# shield_SIM800L_2.net
KiCad netlist of a schematic drawn in EAGLE
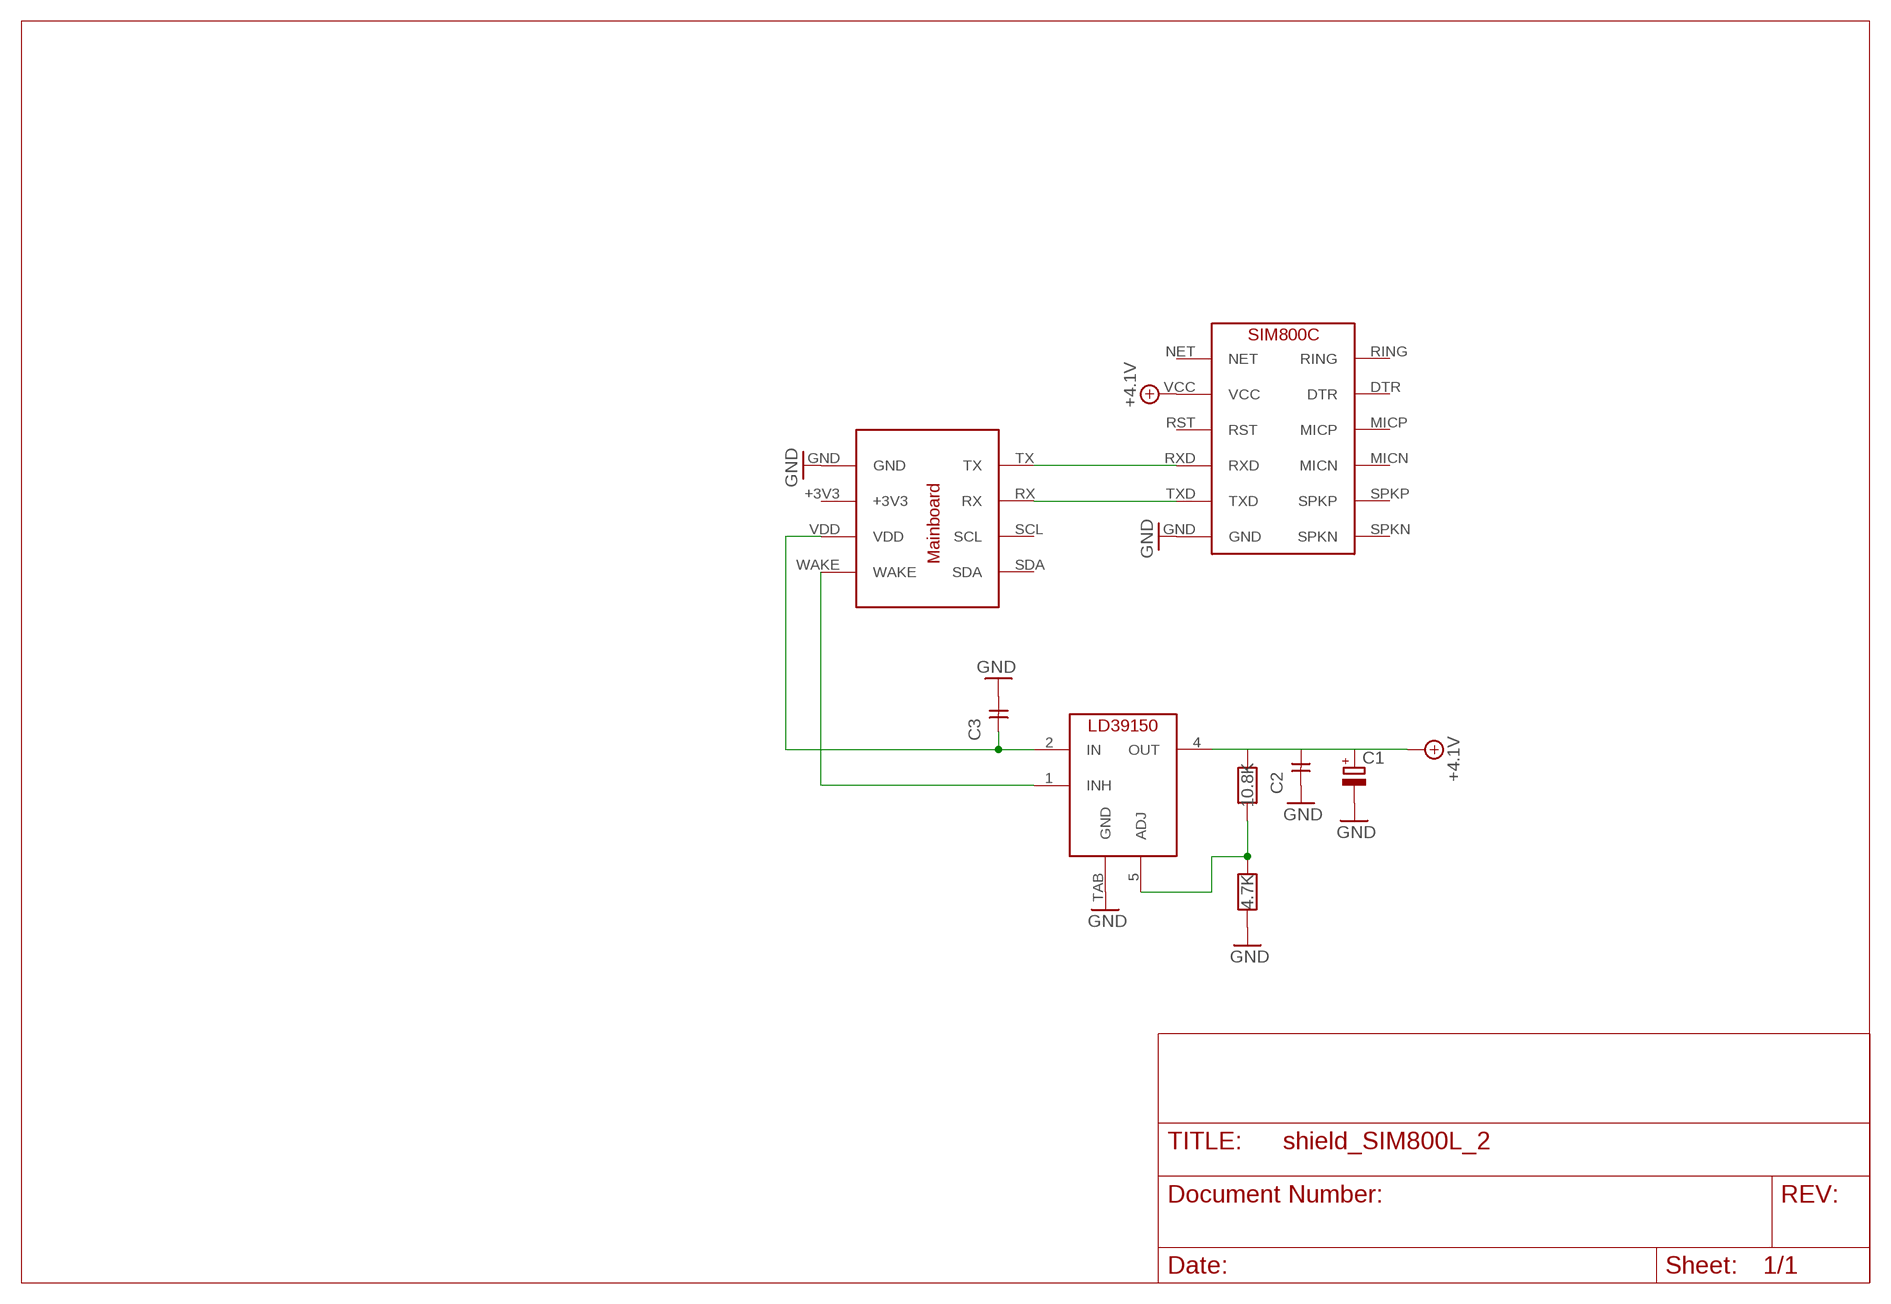
[diagram p0: schematic, sheet 1]

(export (version "E")
  (design (tool "Eeschema 10.0.6"))
  (components
    (comp (ref "C1")
      (value "CPOL-EUE5-13")
      (footprint "eagle-import:E5-13")
      (libsource (lib "eagle-import") (part "CPOL-EUE5-13"))
    )
    (comp (ref "C2")
      (value "CSMD_1206")
      (footprint "eagle-import:SMD_RC_1206")
      (libsource (lib "eagle-import") (part "CSMD_1206"))
    )
    (comp (ref "C3")
      (value "CSMD_1206")
      (footprint "eagle-import:SMD_RC_1206")
      (libsource (lib "eagle-import") (part "CSMD_1206"))
    )
    (comp (ref "R1")
      (value "10.8K")
      (footprint "eagle-import:SMD_RC_1206")
      (libsource (lib "eagle-import") (part "RSMD_1206"))
    )
    (comp (ref "R2")
      (value "4.7K")
      (footprint "eagle-import:SMD_RC_1206")
      (libsource (lib "eagle-import") (part "RSMD_1206"))
    )
    (comp (ref "U$1")
      (value "SHIELD")
      (footprint "eagle-import:SHIELD")
      (libsource (lib "eagle-import") (part "SHIELD"))
    )
    (comp (ref "U$2")
      (value "LD39150PT-R")
      (footprint "eagle-import:PPAK")
      (libsource (lib "eagle-import") (part "LD39150PT-R"))
    )
    (comp (ref "U$6")
      (value "SIM800L")
      (footprint "eagle-import:SIM800L")
      (libsource (lib "eagle-import") (part "SIM800L"))
    )
  )
  (nets
    (net (code "1") (name "+4.1V") (class "Default")
      (node (ref "C1") (pin "+") (pinfunction "+_+") (pintype "passive"))
      (node (ref "C2") (pin "P$2") (pinfunction "2_P$2") (pintype "passive"))
      (node (ref "R1") (pin "P$1") (pinfunction "P$1_P$1") (pintype "passive"))
      (node (ref "U$2") (pin "4") (pinfunction "OUT_4") (pintype "power_in"))
      (node (ref "U$6") (pin "VCC") (pinfunction "VCC_VCC") (pintype "bidirectional"))
    )
    (net (code "2") (name "/+3V3") (class "Default")
      (node (ref "U$1") (pin "+3V3") (pinfunction "+3V3_+3V3") (pintype "power_in"))
    )
    (net (code "3") (name "GND") (class "Default")
      (node (ref "C1") (pin "-") (pinfunction "-_-") (pintype "passive"))
      (node (ref "C2") (pin "P$1") (pinfunction "1_P$1") (pintype "passive"))
      (node (ref "C3") (pin "P$2") (pinfunction "2_P$2") (pintype "passive"))
      (node (ref "R2") (pin "P$2") (pinfunction "P$2_P$2") (pintype "passive"))
      (node (ref "U$1") (pin "GND") (pinfunction "GND_GND") (pintype "power_in"))
      (node (ref "U$2") (pin "TAB") (pinfunction "GND_TAB") (pintype "power_in"))
      (node (ref "U$6") (pin "GND") (pinfunction "GND_GND") (pintype "bidirectional"))
    )
    (net (code "4") (name "Net-(C3-1)") (class "Default")
      (node (ref "C3") (pin "P$1") (pinfunction "1_P$1") (pintype "passive"))
      (node (ref "U$1") (pin "VDD") (pinfunction "VDD_VDD") (pintype "power_in"))
      (node (ref "U$2") (pin "2") (pinfunction "IN_2") (pintype "power_in"))
    )
    (net (code "5") (name "Net-(U$1-PadRX)") (class "Default")
      (node (ref "U$1") (pin "RX") (pinfunction "RX_RX") (pintype "input"))
      (node (ref "U$6") (pin "TXD") (pinfunction "TXD_TXD") (pintype "bidirectional"))
    )
    (net (code "6") (name "Net-(U$1-PadTX)") (class "Default")
      (node (ref "U$1") (pin "TX") (pinfunction "TX_TX") (pintype "output"))
      (node (ref "U$6") (pin "RXD") (pinfunction "RXD_RXD") (pintype "bidirectional"))
    )
    (net (code "7") (name "Net-(U$2-ADJ)") (class "Default")
      (node (ref "R1") (pin "P$2") (pinfunction "P$2_P$2") (pintype "passive"))
      (node (ref "R2") (pin "P$1") (pinfunction "P$1_P$1") (pintype "passive"))
      (node (ref "U$2") (pin "5") (pinfunction "ADJ_5") (pintype "input"))
    )
    (net (code "8") (name "Net-(U$2-INH)") (class "Default")
      (node (ref "U$1") (pin "WAKE") (pinfunction "WAKE_WAKE") (pintype "output"))
      (node (ref "U$2") (pin "1") (pinfunction "INH_1") (pintype "input"))
    )
    (net (code "9") (name "unconnected-(U$1-PadSCL)") (class "Default")
      (node (ref "U$1") (pin "SCL") (pinfunction "SCL_SCL") (pintype "output"))
    )
    (net (code "10") (name "unconnected-(U$1-PadSDA)") (class "Default")
      (node (ref "U$1") (pin "SDA") (pinfunction "SDA_SDA") (pintype "bidirectional"))
    )
    (net (code "11") (name "unconnected-(U$6-PadDTR)") (class "Default")
      (node (ref "U$6") (pin "DTR") (pinfunction "DTR_DTR") (pintype "bidirectional"))
    )
    (net (code "12") (name "unconnected-(U$6-PadMICN)") (class "Default")
      (node (ref "U$6") (pin "MICN") (pinfunction "MICN_MICN") (pintype "bidirectional"))
    )
    (net (code "13") (name "unconnected-(U$6-PadMICP)") (class "Default")
      (node (ref "U$6") (pin "MICP") (pinfunction "MICP_MICP") (pintype "bidirectional"))
    )
    (net (code "14") (name "unconnected-(U$6-PadNET)") (class "Default")
      (node (ref "U$6") (pin "NET") (pinfunction "NET_NET") (pintype "bidirectional"))
    )
    (net (code "15") (name "unconnected-(U$6-PadRING)") (class "Default")
      (node (ref "U$6") (pin "RING") (pinfunction "RING_RING") (pintype "bidirectional"))
    )
    (net (code "16") (name "unconnected-(U$6-PadRST)") (class "Default")
      (node (ref "U$6") (pin "RST") (pinfunction "RST_RST") (pintype "bidirectional"))
    )
    (net (code "17") (name "unconnected-(U$6-PadSPKN)") (class "Default")
      (node (ref "U$6") (pin "SPKN") (pinfunction "SPKN_SPKN") (pintype "bidirectional"))
    )
    (net (code "18") (name "unconnected-(U$6-PadSPKP)") (class "Default")
      (node (ref "U$6") (pin "SPKP") (pinfunction "SPKP_SPKP") (pintype "bidirectional"))
    )
  )
)
